# BMU_schematic.net
KiCad netlist of a schematic drawn in Altium Designer
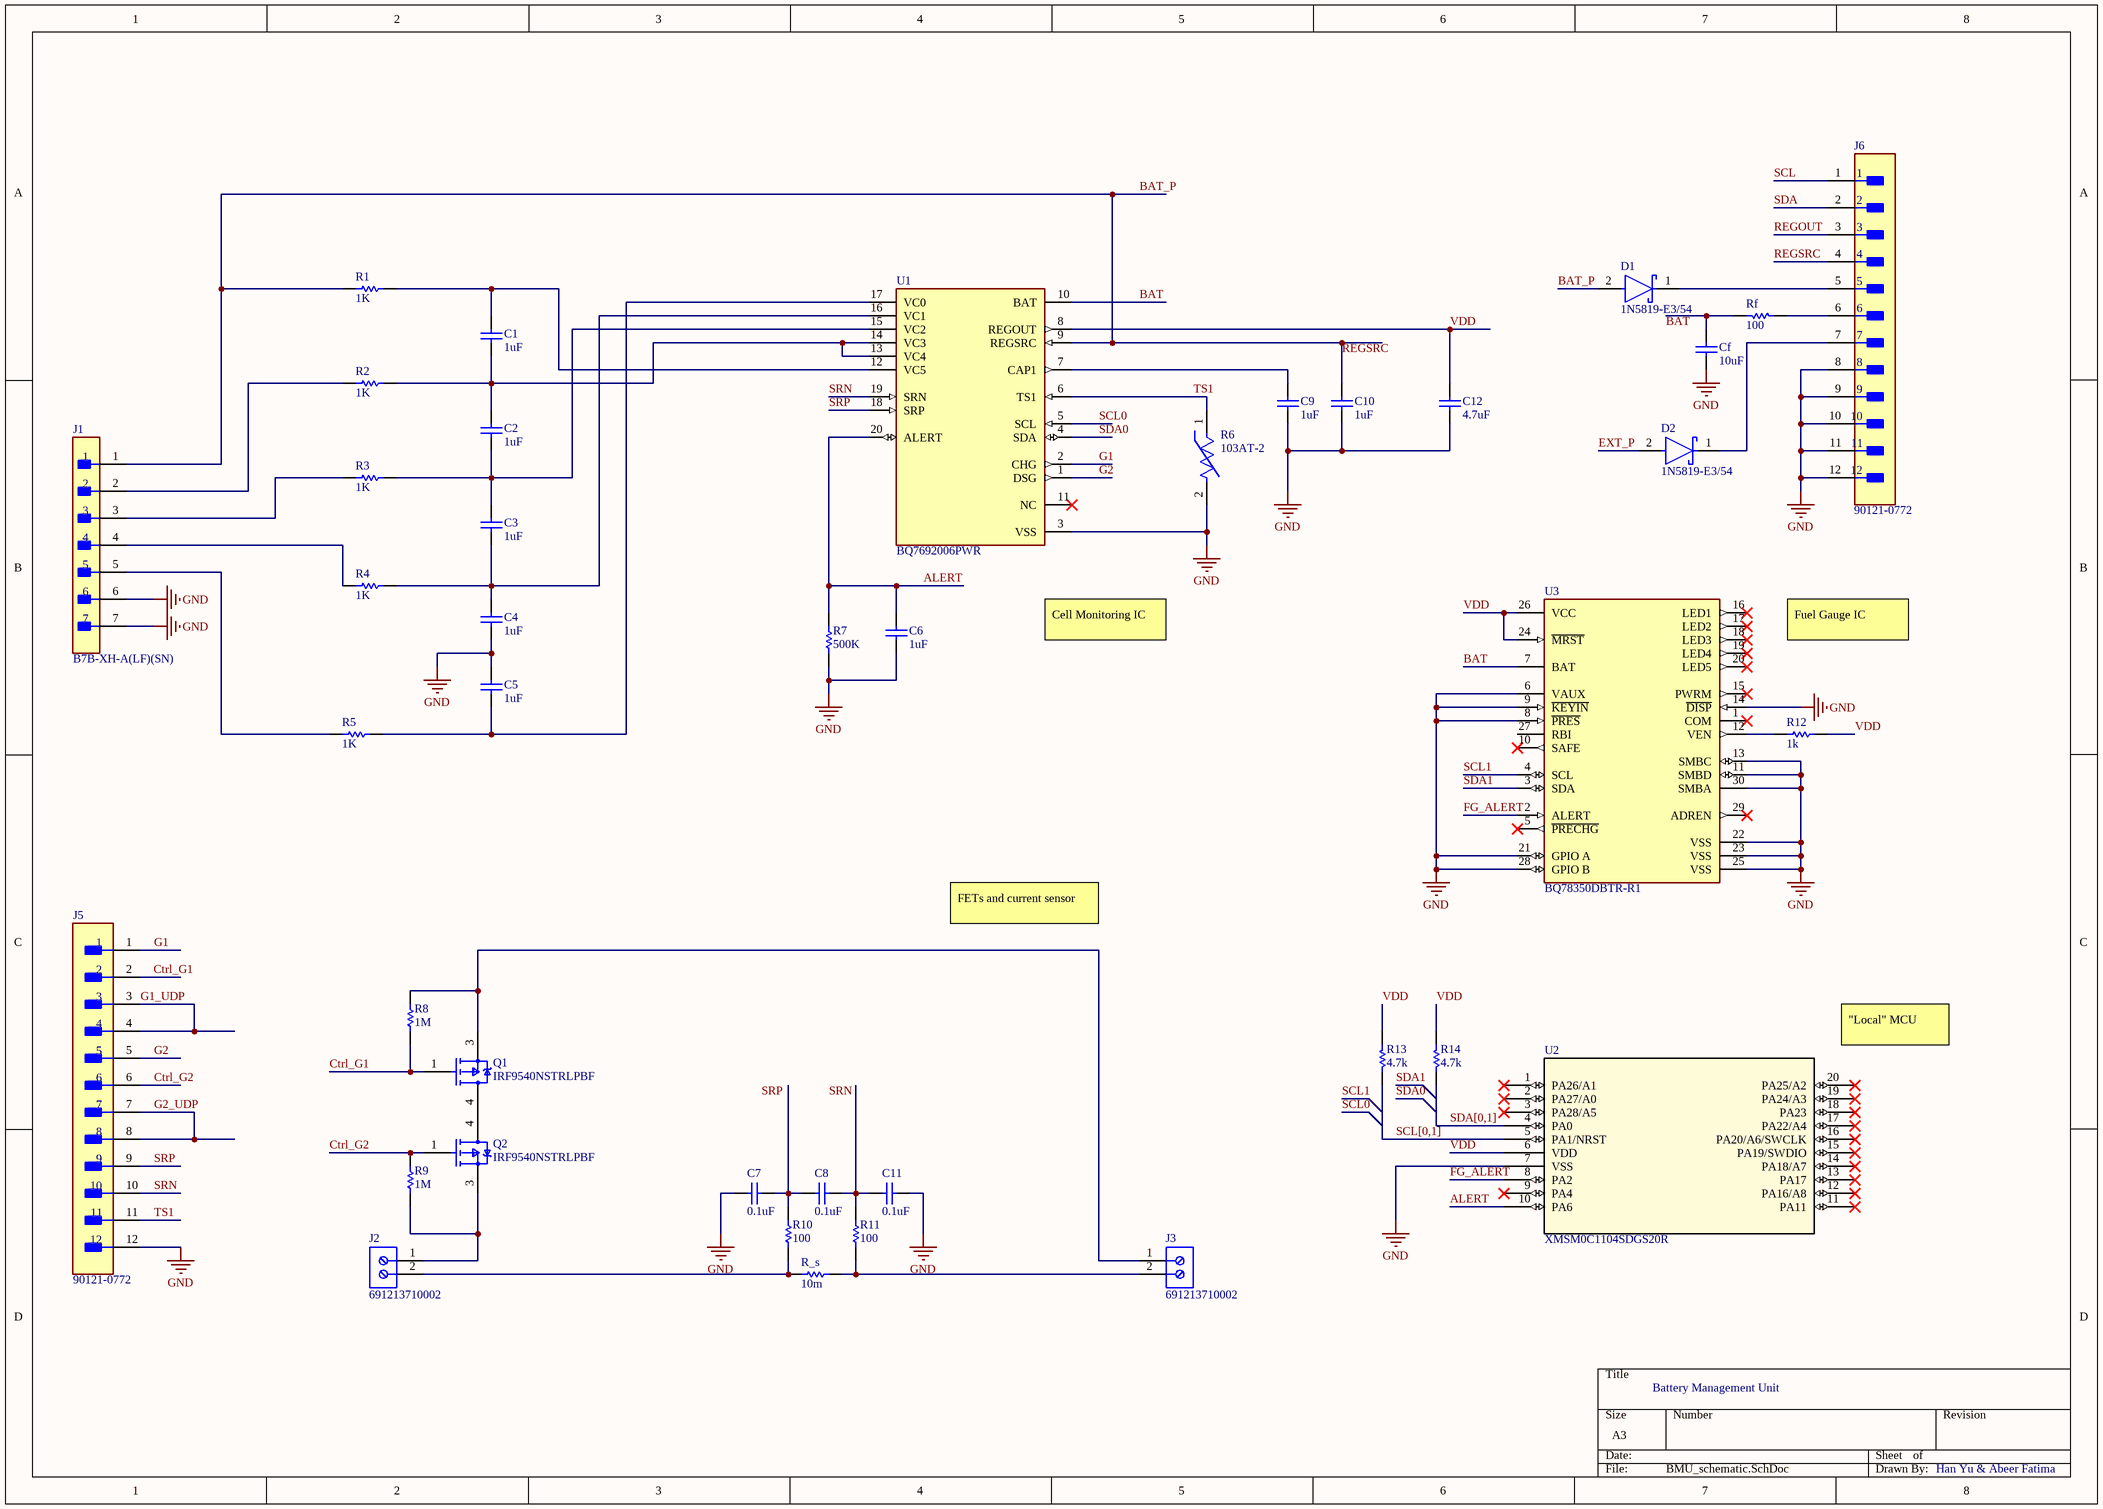
[diagram p0: BMU_schematic.SchDoc]

(export (version "E")
  (design (tool "Eeschema 10.0.6"))
  (components
    (comp (ref "C1")
      (value "1uF")
      (description "Capacitor")
      (libsource (lib "Simulation Generic Components") (part "Capacitor"))
    )
    (comp (ref "C2")
      (value "1uF")
      (description "Capacitor")
      (libsource (lib "Simulation Generic Components") (part "Capacitor"))
    )
    (comp (ref "C3")
      (value "1uF")
      (description "Capacitor")
      (libsource (lib "Simulation Generic Components") (part "Capacitor"))
    )
    (comp (ref "C4")
      (value "1uF")
      (description "Capacitor")
      (libsource (lib "Simulation Generic Components") (part "Capacitor"))
    )
    (comp (ref "C5")
      (value "1uF")
      (description "Capacitor")
      (libsource (lib "Simulation Generic Components") (part "Capacitor"))
    )
    (comp (ref "C6")
      (value "1uF")
      (description "Capacitor")
      (libsource (lib "Simulation Generic Components") (part "Capacitor"))
    )
    (comp (ref "C7")
      (value "0.1uF")
      (description "Capacitor")
      (libsource (lib "Simulation Generic Components") (part "Capacitor"))
    )
    (comp (ref "C8")
      (value "0.1uF")
      (description "Capacitor")
      (libsource (lib "Simulation Generic Components") (part "Capacitor"))
    )
    (comp (ref "C9")
      (value "1uF")
      (description "Capacitor")
      (libsource (lib "Simulation Generic Components") (part "Capacitor"))
    )
    (comp (ref "C10")
      (value "1uF")
      (description "Capacitor")
      (libsource (lib "Simulation Generic Components") (part "Capacitor"))
    )
    (comp (ref "C11")
      (value "0.1uF")
      (description "Capacitor")
      (libsource (lib "Simulation Generic Components") (part "Capacitor"))
    )
    (comp (ref "C12")
      (value "4.7uF")
      (description "Capacitor")
      (libsource (lib "Simulation Generic Components") (part "Capacitor"))
    )
    (comp (ref "Cf")
      (value "10uF")
      (description "Capacitor")
      (libsource (lib "Simulation Generic Components") (part "Capacitor"))
    )
    (comp (ref "D1")
      (value "1N5819-E3/54")
      (footprint "FP-1N5819-E3-54-MFG")
      (description "DIODE SCHOTTKY 40V 1A DO204AL")
      (fields (field (name "VOLTAGE") "40V"))
      (libsource (lib "Altium Content Vault") (part "1d6ec82d83fb6aee721767c19dac4b9"))
    )
    (comp (ref "D2")
      (value "1N5819-E3/54")
      (footprint "FP-1N5819-E3-54-MFG")
      (description "DIODE SCHOTTKY 40V 1A DO204AL")
      (fields (field (name "VOLTAGE") "40V"))
      (libsource (lib "Altium Content Vault") (part "1d6ec82d83fb6aee721767c19dac4b9"))
    )
    (comp (ref "J1")
      (value "B7B-XH-A(LF)(SN)")
      (footprint "FP-B7B-XH-A_LF_SN-MFG")
      (description "CONN HEADER VERT 7POS 2.5MM")
      (libsource (lib "Altium Content Vault") (part "5bcee6b94e1fee4be3f4cc3a650a442"))
    )
    (comp (ref "J2")
      (value "691213710002")
      (footprint "691213710002")
      (fields (field (name "VOLTAGE") "300V"))
      (libsource (lib "Altium Content Vault") (part "TBL - 1R - 02P - Screw"))
    )
    (comp (ref "J3")
      (value "691213710002")
      (footprint "691213710002")
      (fields (field (name "VOLTAGE") "300V"))
      (libsource (lib "Altium Content Vault") (part "TBL - 1R - 02P - Screw"))
    )
    (comp (ref "J5")
      (value "90121-0772")
      (footprint "FP-90121-0772-MFG")
      (description "CONN HEADER R/A 12POS 2.54MM")
      (libsource (lib "") (part "d87d8706af15dcceb0cd5655c97e2e6_1"))
    )
    (comp (ref "J6")
      (value "90121-0772")
      (footprint "FP-90121-0772-MFG")
      (description "CONN HEADER R/A 12POS 2.54MM")
      (libsource (lib "Altium Content Vault") (part "d87d8706af15dcceb0cd5655c97e2e6"))
    )
    (comp (ref "Q1")
      (value "IRF9540NSTRLPBF")
      (footprint "FP-PG-TO263-3-MFG")
      (description "MOSFET P-CH 100V 23A D2PAK")
      (fields
        (field (name "MANUFACTURER") "Infineon")
        (field (name "OCTOPART") "https://octopart.com/irf9540nstrlpbf-infineon-65873776")
      )
      (libsource (lib "Altium Content Vault") (part "141a816ca359c6b7fe1b45081f0b0aa"))
    )
    (comp (ref "Q2")
      (value "IRF9540NSTRLPBF")
      (footprint "FP-PG-TO263-3-MFG")
      (description "MOSFET P-CH 100V 23A D2PAK")
      (fields
        (field (name "MANUFACTURER") "Infineon")
        (field (name "OCTOPART") "https://octopart.com/irf9540nstrlpbf-infineon-65873776")
      )
      (libsource (lib "Altium Content Vault") (part "141a816ca359c6b7fe1b45081f0b0aa"))
    )
    (comp (ref "R1")
      (value "1K")
      (description "Resistor")
      (libsource (lib "Simulation Generic Components") (part "Resistor"))
    )
    (comp (ref "R2")
      (value "1K")
      (description "Resistor")
      (libsource (lib "Simulation Generic Components") (part "Resistor"))
    )
    (comp (ref "R3")
      (value "1K")
      (description "Resistor")
      (libsource (lib "Simulation Generic Components") (part "Resistor"))
    )
    (comp (ref "R4")
      (value "1K")
      (description "Resistor")
      (libsource (lib "Simulation Generic Components") (part "Resistor"))
    )
    (comp (ref "R5")
      (value "1K")
      (description "Resistor")
      (libsource (lib "Simulation Generic Components") (part "Resistor"))
    )
    (comp (ref "R6")
      (value "103AT-2")
      (footprint "FP-103AT-2-MFG")
      (description "Thermistor NTC 10KOhm 1% 2-Pin")
      (fields (field (name "TOLERANCE") "1%"))
      (libsource (lib "Altium Content Vault") (part "3b148a6ebabc5fb4d708a66c052d352"))
    )
    (comp (ref "R7")
      (value "500K")
      (description "Resistor")
      (libsource (lib "Simulation Generic Components") (part "Resistor"))
    )
    (comp (ref "R8")
      (value "1M")
      (description "Resistor")
      (libsource (lib "Simulation Generic Components") (part "Resistor"))
    )
    (comp (ref "R9")
      (value "1M")
      (description "Resistor")
      (libsource (lib "Simulation Generic Components") (part "Resistor"))
    )
    (comp (ref "R10")
      (value "100")
      (description "Resistor")
      (libsource (lib "Simulation Generic Components") (part "Resistor"))
    )
    (comp (ref "R11")
      (value "100")
      (description "Resistor")
      (libsource (lib "Simulation Generic Components") (part "Resistor"))
    )
    (comp (ref "R12")
      (value "1k")
      (description "Resistor")
      (libsource (lib "Simulation Generic Components") (part "Resistor"))
    )
    (comp (ref "R13")
      (value "4.7k")
      (description "Resistor")
      (libsource (lib "Simulation Generic Components") (part "Resistor"))
    )
    (comp (ref "R14")
      (value "4.7k")
      (description "Resistor")
      (libsource (lib "Simulation Generic Components") (part "Resistor"))
    )
    (comp (ref "Rf")
      (value "100")
      (description "Resistor")
      (libsource (lib "Simulation Generic Components") (part "Resistor"))
    )
    (comp (ref "R_s")
      (value "10m")
      (description "Resistor")
      (libsource (lib "Simulation Generic Components") (part "Resistor"))
    )
    (comp (ref "U1")
      (value "BQ7692006PWR")
      (footprint "FP-PW0020A-IPC_B")
      (description "IC BATT MON MULTI 3-5C 20TSSOP")
      (libsource (lib "Altium Content Vault") (part "2737f5332cc9c67ea823bc6cd6859bb"))
    )
    (comp (ref "U2")
      (value "XMSM0C1104SDGS20R")
      (footprint "VSSOP20_DGS_TEX")
      (description "No Description Available")
      (libsource (lib "XMSM0C1104SDGS20R") (part "XMSM0C1104SDGS20R"))
    )
    (comp (ref "U3")
      (value "BQ78350DBTR-R1")
      (footprint "FP-DBT0030A-MFG")
      (description "IC BATTERY MGMT CTRLR 30TSSOP")
      (fields
        (field (name "MANUFACTURER") "Texas Instruments")
        (field (name "OCTOPART") "https://octopart.com/bq78350dbtr-r1-texas+instruments-65758954")
      )
      (libsource (lib "Altium Content Vault") (part "9f0c646d1c849def9bcd27ca6ba4074"))
    )
  )
  (nets
    (net (code "3") (name "/ALERT") (class "Default")
      (node (ref "C6") (pin "2") (pinfunction "2_2") (pintype "passive"))
      (node (ref "R7") (pin "2") (pinfunction "2_2") (pintype "passive"))
      (node (ref "U1") (pin "20") (pinfunction "ALERT_20") (pintype "bidirectional"))
      (node (ref "U2") (pin "10") (pinfunction "PA6_10") (pintype "bidirectional"))
    )
    (net (code "4") (name "/BAT") (class "Default")
      (node (ref "U1") (pin "10") (pinfunction "BAT_10") (pintype "power_in"))
      (node (ref "U3") (pin "7") (pinfunction "BAT_7") (pintype "passive"))
    )
    (net (code "5") (name "/BAT_P") (class "Default")
      (node (ref "C10") (pin "2") (pinfunction "2_2") (pintype "passive"))
      (node (ref "D1") (pin "2") (pinfunction "A_2") (pintype "passive"))
      (node (ref "J1") (pin "1") (pinfunction "1_1") (pintype "passive"))
      (node (ref "J6") (pin "4") (pinfunction "4_4") (pintype "passive"))
      (node (ref "R1") (pin "1") (pinfunction "1_1") (pintype "passive"))
      (node (ref "U1") (pin "9") (pinfunction "REGSRC_9") (pintype "input"))
    )
    (net (code "6") (name "/Ctrl_G1") (class "Default")
      (node (ref "J5") (pin "2") (pinfunction "2_2") (pintype "passive"))
      (node (ref "Q1") (pin "1") (pinfunction "GATE_1") (pintype "passive"))
      (node (ref "R8") (pin "1") (pinfunction "1_1") (pintype "passive"))
    )
    (net (code "7") (name "/Ctrl_G2") (class "Default")
      (node (ref "J5") (pin "6") (pinfunction "6_6") (pintype "passive"))
      (node (ref "Q2") (pin "1") (pinfunction "GATE_1") (pintype "passive"))
      (node (ref "R9") (pin "2") (pinfunction "2_2") (pintype "passive"))
    )
    (net (code "8") (name "/EXT_P") (class "Default")
      (node (ref "D2") (pin "2") (pinfunction "A_2") (pintype "passive"))
    )
    (net (code "9") (name "/FG_ALERT") (class "Default")
      (node (ref "U2") (pin "8") (pinfunction "PA2_8") (pintype "bidirectional"))
      (node (ref "U3") (pin "2") (pinfunction "ALERT_2") (pintype "input"))
    )
    (net (code "10") (name "/G1") (class "Default")
      (node (ref "J5") (pin "1") (pinfunction "1_1") (pintype "passive"))
      (node (ref "U1") (pin "2") (pinfunction "CHG_2") (pintype "output"))
    )
    (net (code "11") (name "/G1_UDP") (class "Default")
      (node (ref "J5") (pin "3") (pinfunction "3_3") (pintype "passive"))
      (node (ref "J5") (pin "4") (pinfunction "4_4") (pintype "passive"))
    )
    (net (code "12") (name "/G2") (class "Default")
      (node (ref "J5") (pin "5") (pinfunction "5_5") (pintype "passive"))
      (node (ref "U1") (pin "1") (pinfunction "DSG_1") (pintype "output"))
    )
    (net (code "13") (name "/G2_UDP") (class "Default")
      (node (ref "J5") (pin "7") (pinfunction "7_7") (pintype "passive"))
      (node (ref "J5") (pin "8") (pinfunction "8_8") (pintype "passive"))
    )
    (net (code "14") (name "/REGOUT") (class "Default")
      (node (ref "J6") (pin "3") (pinfunction "3_3") (pintype "passive"))
    )
    (net (code "15") (name "/SCL") (class "Default")
      (node (ref "J6") (pin "1") (pinfunction "1_1") (pintype "passive"))
    )
    (net (code "16") (name "/SCL0") (class "Default")
      (node (ref "U1") (pin "5") (pinfunction "SCL_5") (pintype "input"))
    )
    (net (code "17") (name "/SCL1") (class "Default")
      (node (ref "U3") (pin "4") (pinfunction "SCL_4") (pintype "bidirectional"))
    )
    (net (code "18") (name "/SDA") (class "Default")
      (node (ref "J6") (pin "2") (pinfunction "2_2") (pintype "passive"))
    )
    (net (code "19") (name "/SDA0") (class "Default")
      (node (ref "U1") (pin "4") (pinfunction "SDA_4") (pintype "bidirectional"))
    )
    (net (code "20") (name "/SDA1") (class "Default")
      (node (ref "U3") (pin "3") (pinfunction "SDA_3") (pintype "bidirectional"))
    )
    (net (code "21") (name "/SRN") (class "Default")
      (node (ref "J5") (pin "10") (pinfunction "10_10") (pintype "passive"))
      (node (ref "U1") (pin "19") (pinfunction "SRN_19") (pintype "input"))
    )
    (net (code "22") (name "/SRP") (class "Default")
      (node (ref "J5") (pin "9") (pinfunction "9_9") (pintype "passive"))
      (node (ref "U1") (pin "18") (pinfunction "SRP_18") (pintype "input"))
    )
    (net (code "23") (name "/TS1") (class "Default")
      (node (ref "J5") (pin "11") (pinfunction "11_11") (pintype "passive"))
      (node (ref "R6") (pin "1") (pinfunction "1_1") (pintype "passive"))
      (node (ref "U1") (pin "6") (pinfunction "TS1_6") (pintype "input"))
    )
    (net (code "24") (name "/VDD") (class "Default")
      (node (ref "C12") (pin "2") (pinfunction "2_2") (pintype "passive"))
      (node (ref "R12") (pin "2") (pinfunction "2_2") (pintype "passive"))
      (node (ref "R13") (pin "2") (pinfunction "2_2") (pintype "passive"))
      (node (ref "R14") (pin "2") (pinfunction "2_2") (pintype "passive"))
      (node (ref "U1") (pin "8") (pinfunction "REGOUT_8") (pintype "output"))
      (node (ref "U2") (pin "6") (pinfunction "VDD_6") (pintype "power_in"))
      (node (ref "U3") (pin "24") (pinfunction "~{MRST}_24") (pintype "input"))
      (node (ref "U3") (pin "26") (pinfunction "VCC_26") (pintype "power_in"))
    )
    (net (code "25") (name "/{\"SCL[0,1]\"}") (class "Default")
      (node (ref "U2") (pin "5") (pinfunction "PA1/NRST_5") (pintype "bidirectional"))
    )
    (net (code "26") (name "/{\"SDA[0,1]\"}") (class "Default")
      (node (ref "U2") (pin "4") (pinfunction "PA0_4") (pintype "bidirectional"))
    )
    (net (code "27") (name "GND") (class "Default")
      (node (ref "C10") (pin "1") (pinfunction "1_1") (pintype "passive"))
      (node (ref "C11") (pin "1") (pinfunction "1_1") (pintype "passive"))
      (node (ref "C12") (pin "1") (pinfunction "1_1") (pintype "passive"))
      (node (ref "C4") (pin "1") (pinfunction "1_1") (pintype "passive"))
      (node (ref "C5") (pin "2") (pinfunction "2_2") (pintype "passive"))
      (node (ref "C6") (pin "1") (pinfunction "1_1") (pintype "passive"))
      (node (ref "C7") (pin "2") (pinfunction "2_2") (pintype "passive"))
      (node (ref "C9") (pin "1") (pinfunction "1_1") (pintype "passive"))
      (node (ref "Cf") (pin "1") (pinfunction "1_1") (pintype "passive"))
      (node (ref "J1") (pin "6") (pinfunction "6_6") (pintype "passive"))
      (node (ref "J1") (pin "7") (pinfunction "7_7") (pintype "passive"))
      (node (ref "J5") (pin "12") (pinfunction "12_12") (pintype "passive"))
      (node (ref "J6") (pin "10") (pinfunction "10_10") (pintype "passive"))
      (node (ref "J6") (pin "11") (pinfunction "11_11") (pintype "passive"))
      (node (ref "J6") (pin "12") (pinfunction "12_12") (pintype "passive"))
      (node (ref "J6") (pin "8") (pinfunction "8_8") (pintype "passive"))
      (node (ref "J6") (pin "9") (pinfunction "9_9") (pintype "passive"))
      (node (ref "R6") (pin "2") (pinfunction "2_2") (pintype "passive"))
      (node (ref "R7") (pin "1") (pinfunction "1_1") (pintype "passive"))
      (node (ref "U1") (pin "3") (pinfunction "VSS_3") (pintype "passive"))
      (node (ref "U2") (pin "7") (pinfunction "VSS_7") (pintype "power_in"))
      (node (ref "U3") (pin "11") (pinfunction "SMBD_11") (pintype "bidirectional"))
      (node (ref "U3") (pin "13") (pinfunction "SMBC_13") (pintype "bidirectional"))
      (node (ref "U3") (pin "14") (pinfunction "~{DISP}_14") (pintype "input"))
      (node (ref "U3") (pin "21") (pinfunction "GPIO_A_21") (pintype "bidirectional"))
      (node (ref "U3") (pin "22") (pinfunction "VSS_22") (pintype "power_in"))
      (node (ref "U3") (pin "23") (pinfunction "VSS_23") (pintype "power_in"))
      (node (ref "U3") (pin "25") (pinfunction "VSS_25") (pintype "power_in"))
      (node (ref "U3") (pin "28") (pinfunction "GPIO_B_28") (pintype "bidirectional"))
      (node (ref "U3") (pin "30") (pinfunction "SMBA_30") (pintype "passive"))
      (node (ref "U3") (pin "6") (pinfunction "VAUX_6") (pintype "passive"))
      (node (ref "U3") (pin "8") (pinfunction "~{PRES}_8") (pintype "input"))
      (node (ref "U3") (pin "9") (pinfunction "~{KEYIN}_9") (pintype "input"))
    )
    (net (code "28") (name "Net-(C7-Pad1)") (class "Default")
      (node (ref "C7") (pin "1") (pinfunction "1_1") (pintype "passive"))
      (node (ref "C8") (pin "2") (pinfunction "2_2") (pintype "passive"))
      (node (ref "R10") (pin "2") (pinfunction "2_2") (pintype "passive"))
    )
    (net (code "29") (name "Net-(C11-Pad2)") (class "Default")
      (node (ref "C11") (pin "2") (pinfunction "2_2") (pintype "passive"))
      (node (ref "C8") (pin "1") (pinfunction "1_1") (pintype "passive"))
      (node (ref "R11") (pin "2") (pinfunction "2_2") (pintype "passive"))
    )
    (net (code "30") (name "Net-(Cf-Pad2)") (class "Default")
      (node (ref "Cf") (pin "2") (pinfunction "2_2") (pintype "passive"))
      (node (ref "Rf") (pin "2") (pinfunction "2_2") (pintype "passive"))
    )
    (net (code "31") (name "Net-(D1-C)") (class "Default")
      (node (ref "D1") (pin "1") (pinfunction "C_1") (pintype "passive"))
      (node (ref "J6") (pin "5") (pinfunction "5_5") (pintype "passive"))
    )
    (net (code "32") (name "Net-(D2-C)") (class "Default")
      (node (ref "D2") (pin "1") (pinfunction "C_1") (pintype "passive"))
      (node (ref "J6") (pin "7") (pinfunction "7_7") (pintype "passive"))
    )
    (net (code "33") (name "Net-(J1-Pad2)") (class "Default")
      (node (ref "J1") (pin "2") (pinfunction "2_2") (pintype "passive"))
      (node (ref "R2") (pin "1") (pinfunction "1_1") (pintype "passive"))
    )
    (net (code "34") (name "Net-(J1-Pad3)") (class "Default")
      (node (ref "J1") (pin "3") (pinfunction "3_3") (pintype "passive"))
      (node (ref "R3") (pin "1") (pinfunction "1_1") (pintype "passive"))
    )
    (net (code "35") (name "Net-(J1-Pad4)") (class "Default")
      (node (ref "J1") (pin "4") (pinfunction "4_4") (pintype "passive"))
      (node (ref "R4") (pin "1") (pinfunction "1_1") (pintype "passive"))
    )
    (net (code "36") (name "Net-(J1-Pad5)") (class "Default")
      (node (ref "J1") (pin "5") (pinfunction "5_5") (pintype "passive"))
      (node (ref "R5") (pin "1") (pinfunction "1_1") (pintype "passive"))
    )
    (net (code "37") (name "Net-(J2-Pad2)") (class "Default")
      (node (ref "J2") (pin "2") (pinfunction "2_2") (pintype "passive"))
      (node (ref "R10") (pin "1") (pinfunction "1_1") (pintype "passive"))
      (node (ref "R_s") (pin "1") (pinfunction "1_1") (pintype "passive"))
    )
    (net (code "38") (name "Net-(J3-Pad2)") (class "Default")
      (node (ref "J3") (pin "2") (pinfunction "2_2") (pintype "passive"))
      (node (ref "R11") (pin "1") (pinfunction "1_1") (pintype "passive"))
      (node (ref "R_s") (pin "2") (pinfunction "2_2") (pintype "passive"))
    )
    (net (code "39") (name "Net-(J6-Pad6)") (class "Default")
      (node (ref "J6") (pin "6") (pinfunction "6_6") (pintype "passive"))
      (node (ref "Rf") (pin "1") (pinfunction "1_1") (pintype "passive"))
    )
    (net (code "40") (name "Net-(Q1-DRAIN)") (class "Default")
      (node (ref "Q1") (pin "4") (pinfunction "DRAIN_4") (pintype "passive"))
      (node (ref "Q2") (pin "4") (pinfunction "DRAIN_4") (pintype "passive"))
    )
    (net (code "41") (name "Net-(Q1-SOURCE)") (class "Default")
      (node (ref "J3") (pin "1") (pinfunction "1_1") (pintype "passive"))
      (node (ref "Q1") (pin "3") (pinfunction "SOURCE_3") (pintype "passive"))
      (node (ref "R8") (pin "2") (pinfunction "2_2") (pintype "passive"))
    )
    (net (code "42") (name "Net-(Q2-SOURCE)") (class "Default")
      (node (ref "J2") (pin "1") (pinfunction "1_1") (pintype "passive"))
      (node (ref "Q2") (pin "3") (pinfunction "SOURCE_3") (pintype "passive"))
      (node (ref "R9") (pin "1") (pinfunction "1_1") (pintype "passive"))
    )
    (net (code "43") (name "Net-(U1-CAP1)") (class "Default")
      (node (ref "C9") (pin "2") (pinfunction "2_2") (pintype "passive"))
      (node (ref "U1") (pin "7") (pinfunction "CAP1_7") (pintype "output"))
    )
    (net (code "44") (name "Net-(U1-VC0)") (class "Default")
      (node (ref "C5") (pin "1") (pinfunction "1_1") (pintype "passive"))
      (node (ref "R5") (pin "2") (pinfunction "2_2") (pintype "passive"))
      (node (ref "U1") (pin "17") (pinfunction "VC0_17") (pintype "passive"))
    )
    (net (code "45") (name "Net-(U1-VC1)") (class "Default")
      (node (ref "C3") (pin "1") (pinfunction "1_1") (pintype "passive"))
      (node (ref "C4") (pin "2") (pinfunction "2_2") (pintype "passive"))
      (node (ref "R4") (pin "2") (pinfunction "2_2") (pintype "passive"))
      (node (ref "U1") (pin "16") (pinfunction "VC1_16") (pintype "passive"))
    )
    (net (code "46") (name "Net-(U1-VC2)") (class "Default")
      (node (ref "C2") (pin "1") (pinfunction "1_1") (pintype "passive"))
      (node (ref "C3") (pin "2") (pinfunction "2_2") (pintype "passive"))
      (node (ref "R3") (pin "2") (pinfunction "2_2") (pintype "passive"))
      (node (ref "U1") (pin "15") (pinfunction "VC2_15") (pintype "passive"))
    )
    (net (code "47") (name "Net-(U1-VC3)") (class "Default")
      (node (ref "C1") (pin "1") (pinfunction "1_1") (pintype "passive"))
      (node (ref "C2") (pin "2") (pinfunction "2_2") (pintype "passive"))
      (node (ref "R2") (pin "2") (pinfunction "2_2") (pintype "passive"))
      (node (ref "U1") (pin "13") (pinfunction "VC4_13") (pintype "passive"))
      (node (ref "U1") (pin "14") (pinfunction "VC3_14") (pintype "passive"))
    )
    (net (code "48") (name "Net-(U1-VC5)") (class "Default")
      (node (ref "C1") (pin "2") (pinfunction "2_2") (pintype "passive"))
      (node (ref "R1") (pin "2") (pinfunction "2_2") (pintype "passive"))
      (node (ref "U1") (pin "12") (pinfunction "VC5_12") (pintype "passive"))
    )
    (net (code "49") (name "Net-(U3-VEN)") (class "Default")
      (node (ref "R12") (pin "1") (pinfunction "1_1") (pintype "passive"))
      (node (ref "U3") (pin "12") (pinfunction "VEN_12") (pintype "output"))
    )
    (net (code "50") (name "unconnected-(R13-Pad1)") (class "Default")
      (node (ref "R13") (pin "1") (pinfunction "1_1") (pintype "passive"))
    )
    (net (code "51") (name "unconnected-(R14-Pad1)") (class "Default")
      (node (ref "R14") (pin "1") (pinfunction "1_1") (pintype "passive"))
    )
    (net (code "52") (name "unconnected-(U1-NC-Pad11)") (class "Default")
      (node (ref "U1") (pin "11") (pinfunction "NC_11") (pintype "passive+no_connect"))
    )
    (net (code "53") (name "unconnected-(U2-PA4-Pad9)") (class "Default")
      (node (ref "U2") (pin "9") (pinfunction "PA4_9") (pintype "bidirectional+no_connect"))
    )
    (net (code "54") (name "unconnected-(U2-PA11-Pad11)") (class "Default")
      (node (ref "U2") (pin "11") (pinfunction "PA11_11") (pintype "bidirectional+no_connect"))
    )
    (net (code "55") (name "unconnected-(U2-PA16{slash}A8-Pad12)") (class "Default")
      (node (ref "U2") (pin "12") (pinfunction "PA16/A8_12") (pintype "bidirectional+no_connect"))
    )
    (net (code "56") (name "unconnected-(U2-PA17-Pad13)") (class "Default")
      (node (ref "U2") (pin "13") (pinfunction "PA17_13") (pintype "bidirectional+no_connect"))
    )
    (net (code "57") (name "unconnected-(U2-PA18{slash}A7-Pad14)") (class "Default")
      (node (ref "U2") (pin "14") (pinfunction "PA18/A7_14") (pintype "bidirectional+no_connect"))
    )
    (net (code "58") (name "unconnected-(U2-PA19{slash}SWDIO-Pad15)") (class "Default")
      (node (ref "U2") (pin "15") (pinfunction "PA19/SWDIO_15") (pintype "bidirectional+no_connect"))
    )
    (net (code "59") (name "unconnected-(U2-PA20{slash}A6{slash}SWCLK-Pad16)") (class "Default")
      (node (ref "U2") (pin "16") (pinfunction "PA20/A6/SWCLK_16") (pintype "bidirectional+no_connect"))
    )
    (net (code "60") (name "unconnected-(U2-PA22{slash}A4-Pad17)") (class "Default")
      (node (ref "U2") (pin "17") (pinfunction "PA22/A4_17") (pintype "bidirectional+no_connect"))
    )
    (net (code "61") (name "unconnected-(U2-PA23-Pad18)") (class "Default")
      (node (ref "U2") (pin "18") (pinfunction "PA23_18") (pintype "bidirectional+no_connect"))
    )
    (net (code "62") (name "unconnected-(U2-PA24{slash}A3-Pad19)") (class "Default")
      (node (ref "U2") (pin "19") (pinfunction "PA24/A3_19") (pintype "bidirectional+no_connect"))
    )
    (net (code "63") (name "unconnected-(U2-PA25{slash}A2-Pad20)") (class "Default")
      (node (ref "U2") (pin "20") (pinfunction "PA25/A2_20") (pintype "bidirectional+no_connect"))
    )
    (net (code "64") (name "unconnected-(U2-PA26{slash}A1-Pad1)") (class "Default")
      (node (ref "U2") (pin "1") (pinfunction "PA26/A1_1") (pintype "bidirectional+no_connect"))
    )
    (net (code "65") (name "unconnected-(U2-PA27{slash}A0-Pad2)") (class "Default")
      (node (ref "U2") (pin "2") (pinfunction "PA27/A0_2") (pintype "bidirectional+no_connect"))
    )
    (net (code "66") (name "unconnected-(U2-PA28{slash}A5-Pad3)") (class "Default")
      (node (ref "U2") (pin "3") (pinfunction "PA28/A5_3") (pintype "bidirectional+no_connect"))
    )
    (net (code "67") (name "unconnected-(U3-ADREN-Pad29)") (class "Default")
      (node (ref "U3") (pin "29") (pinfunction "ADREN_29") (pintype "output+no_connect"))
    )
    (net (code "68") (name "unconnected-(U3-COM-Pad1)") (class "Default")
      (node (ref "U3") (pin "1") (pinfunction "COM_1") (pintype "open_collector+no_connect"))
    )
    (net (code "69") (name "unconnected-(U3-LED1-Pad16)") (class "Default")
      (node (ref "U3") (pin "16") (pinfunction "LED1_16") (pintype "output+no_connect"))
    )
    (net (code "70") (name "unconnected-(U3-LED2-Pad17)") (class "Default")
      (node (ref "U3") (pin "17") (pinfunction "LED2_17") (pintype "output+no_connect"))
    )
    (net (code "71") (name "unconnected-(U3-LED3-Pad18)") (class "Default")
      (node (ref "U3") (pin "18") (pinfunction "LED3_18") (pintype "output+no_connect"))
    )
    (net (code "72") (name "unconnected-(U3-LED4-Pad19)") (class "Default")
      (node (ref "U3") (pin "19") (pinfunction "LED4_19") (pintype "output+no_connect"))
    )
    (net (code "73") (name "unconnected-(U3-LED5-Pad20)") (class "Default")
      (node (ref "U3") (pin "20") (pinfunction "LED5_20") (pintype "output+no_connect"))
    )
    (net (code "74") (name "unconnected-(U3-PWRM-Pad15)") (class "Default")
      (node (ref "U3") (pin "15") (pinfunction "PWRM_15") (pintype "output+no_connect"))
    )
    (net (code "75") (name "unconnected-(U3-RBI-Pad27)") (class "Default")
      (node (ref "U3") (pin "27") (pinfunction "RBI_27") (pintype "passive"))
    )
    (net (code "76") (name "unconnected-(U3-SAFE-Pad10)") (class "Default")
      (node (ref "U3") (pin "10") (pinfunction "SAFE_10") (pintype "output+no_connect"))
    )
    (net (code "77") (name "unconnected-(U3-~{PRECHG}-Pad5)") (class "Default")
      (node (ref "U3") (pin "5") (pinfunction "~{PRECHG}_5") (pintype "output+no_connect"))
    )
  )
)
